# MINIRACER-SD-USB.net
KiCad netlist of a schematic drawn in Altium Designer
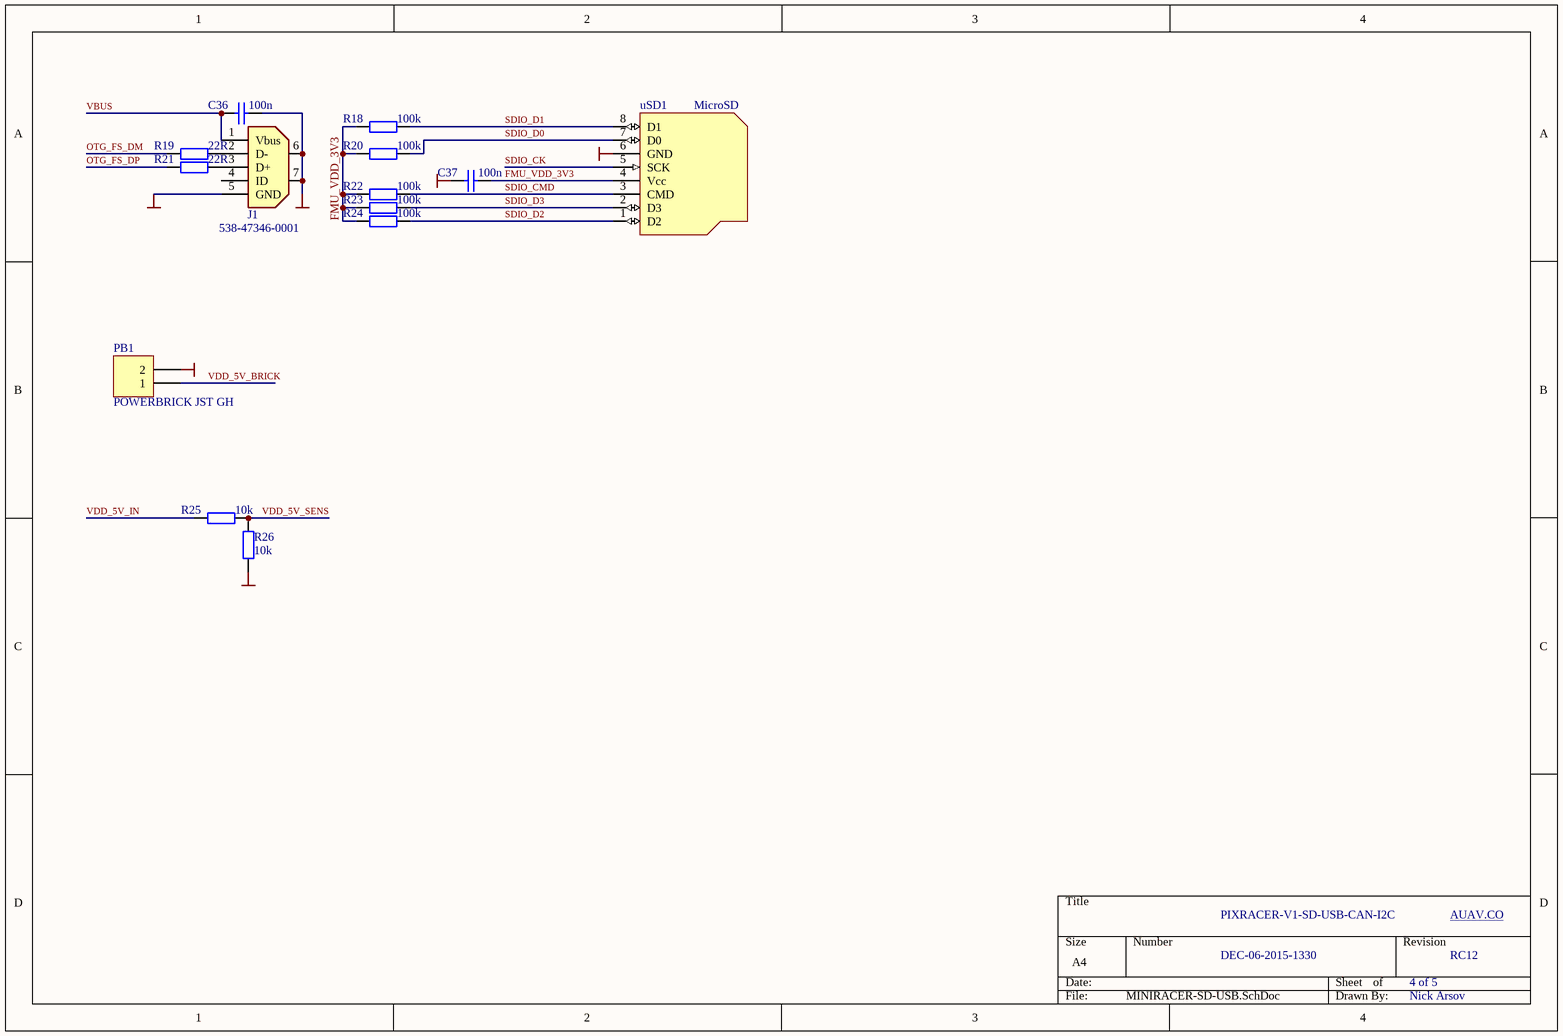
[diagram p0: MINIRACER-SD-USB.SchDoc]

(export (version "E")
  (design (tool "Eeschema 10.0.6"))
  (components
    (comp (ref "C36")
      (value "100n")
      (footprint "0402A")
      (description "Capacitor")
      (fields (field (name "PUBLISHER") "Altium Limited"))
      (libsource (lib "Miscellaneous Devices") (part "Cap"))
    )
    (comp (ref "C37")
      (value "100n")
      (footprint "0402A")
      (description "Capacitor")
      (fields (field (name "PUBLISHER") "Altium Limited"))
      (libsource (lib "Miscellaneous Devices") (part "Cap"))
    )
    (comp (ref "J1")
      (value "miniUSB")
      (footprint "USBmicro_B")
      (fields (field (name "MOUSER PART NUMBER") "538-47346-0001"))
      (libsource (lib "My_Altium") (part "MicroUSB"))
    )
    (comp (ref "PB1")
      (value "POWERBRICK JST GH")
      (footprint "HDR1X2")
      (description "Header, 2-Pin")
      (fields (field (name "PUBLISHER") "Altium Limited"))
      (libsource (lib "Miscellaneous Connectors") (part "Header 2"))
    )
    (comp (ref "R18")
      (value "100k")
      (footprint "0402A")
      (description "Resistor")
      (fields (field (name "PUBLISHER") "Altium Limited"))
      (libsource (lib "Miscellaneous Devices") (part "Res2"))
    )
    (comp (ref "R19")
      (value "22R")
      (footprint "0402A")
      (description "Resistor")
      (fields (field (name "PUBLISHER") "Altium Limited"))
      (libsource (lib "Miscellaneous Devices") (part "Res2"))
    )
    (comp (ref "R20")
      (value "100k")
      (footprint "0402A")
      (description "Resistor")
      (fields (field (name "PUBLISHER") "Altium Limited"))
      (libsource (lib "Miscellaneous Devices") (part "Res2"))
    )
    (comp (ref "R21")
      (value "22R")
      (footprint "0402A")
      (description "Resistor")
      (fields (field (name "PUBLISHER") "Altium Limited"))
      (libsource (lib "Miscellaneous Devices") (part "Res2"))
    )
    (comp (ref "R22")
      (value "100k")
      (footprint "0402A")
      (description "Resistor")
      (fields (field (name "PUBLISHER") "Altium Limited"))
      (libsource (lib "Miscellaneous Devices") (part "Res2"))
    )
    (comp (ref "R23")
      (value "100k")
      (footprint "0402A")
      (description "Resistor")
      (fields (field (name "PUBLISHER") "Altium Limited"))
      (libsource (lib "Miscellaneous Devices") (part "Res2"))
    )
    (comp (ref "R24")
      (value "100k")
      (footprint "0402A")
      (description "Resistor")
      (fields (field (name "PUBLISHER") "Altium Limited"))
      (libsource (lib "Miscellaneous Devices") (part "Res2"))
    )
    (comp (ref "R25")
      (value "10k")
      (footprint "0402A")
      (description "Resistor")
      (fields (field (name "PUBLISHER") "Altium Limited"))
      (libsource (lib "Miscellaneous Devices") (part "Res2"))
    )
    (comp (ref "R26")
      (value "10k")
      (footprint "0402A")
      (description "Resistor")
      (fields (field (name "PUBLISHER") "Altium Limited"))
      (libsource (lib "") (part "Res2_1"))
    )
    (comp (ref "uSD1")
      (value "MicroSD")
      (footprint "MicroSD_China_01")
      (libsource (lib "My_Altium") (part "MicroSD"))
    )
  )
  (nets
    (net (code "1") (name "/FMU_VDD_3V3") (class "Default")
      (node (ref "C37") (pin "1") (pinfunction "1_1") (pintype "passive"))
      (node (ref "R18") (pin "2") (pinfunction "2_2") (pintype "passive"))
      (node (ref "R20") (pin "2") (pinfunction "2_2") (pintype "passive"))
      (node (ref "R22") (pin "2") (pinfunction "2_2") (pintype "passive"))
      (node (ref "R23") (pin "2") (pinfunction "2_2") (pintype "passive"))
      (node (ref "R24") (pin "2") (pinfunction "2_2") (pintype "passive"))
      (node (ref "uSD1") (pin "4") (pinfunction "Vcc_4") (pintype "power_in"))
    )
    (net (code "2") (name "/OTG_FS_DM") (class "Default")
      (node (ref "R19") (pin "2") (pinfunction "2_2") (pintype "passive"))
    )
    (net (code "3") (name "/OTG_FS_DP") (class "Default")
      (node (ref "R21") (pin "2") (pinfunction "2_2") (pintype "passive"))
    )
    (net (code "4") (name "/SDIO_CK") (class "Default")
      (node (ref "uSD1") (pin "5") (pinfunction "SCK_5") (pintype "input"))
    )
    (net (code "5") (name "/SDIO_CMD") (class "Default")
      (node (ref "R22") (pin "1") (pinfunction "1_1") (pintype "passive"))
      (node (ref "uSD1") (pin "3") (pinfunction "CMD_3") (pintype "passive"))
    )
    (net (code "6") (name "/SDIO_D0") (class "Default")
      (node (ref "R20") (pin "1") (pinfunction "1_1") (pintype "passive"))
      (node (ref "uSD1") (pin "7") (pinfunction "D0_7") (pintype "bidirectional"))
    )
    (net (code "7") (name "/SDIO_D1") (class "Default")
      (node (ref "R18") (pin "1") (pinfunction "1_1") (pintype "passive"))
      (node (ref "uSD1") (pin "8") (pinfunction "D1_8") (pintype "bidirectional"))
    )
    (net (code "8") (name "/SDIO_D2") (class "Default")
      (node (ref "R24") (pin "1") (pinfunction "1_1") (pintype "passive"))
      (node (ref "uSD1") (pin "1") (pinfunction "D2_1") (pintype "bidirectional"))
    )
    (net (code "9") (name "/SDIO_D3") (class "Default")
      (node (ref "R23") (pin "1") (pinfunction "1_1") (pintype "passive"))
      (node (ref "uSD1") (pin "2") (pinfunction "D3_2") (pintype "bidirectional"))
    )
    (net (code "10") (name "/VBUS") (class "Default")
      (node (ref "C36") (pin "2") (pinfunction "2_2") (pintype "passive"))
      (node (ref "J1") (pin "1") (pinfunction "Vbus_1") (pintype "power_in"))
    )
    (net (code "11") (name "/VDD_5V_BRICK") (class "Default")
      (node (ref "PB1") (pin "1") (pinfunction "1_1") (pintype "passive"))
    )
    (net (code "12") (name "/VDD_5V_IN") (class "Default")
      (node (ref "R25") (pin "2") (pinfunction "2_2") (pintype "passive"))
    )
    (net (code "13") (name "/VDD_5V_SENS") (class "Default")
      (node (ref "R25") (pin "1") (pinfunction "1_1") (pintype "passive"))
      (node (ref "R26") (pin "1") (pinfunction "1_1") (pintype "passive"))
    )
    (net (code "14") (name "GND") (class "Default")
      (node (ref "C36") (pin "1") (pinfunction "1_1") (pintype "passive"))
      (node (ref "C37") (pin "2") (pinfunction "2_2") (pintype "passive"))
      (node (ref "J1") (pin "5") (pinfunction "GND_5") (pintype "power_in"))
      (node (ref "J1") (pin "6") (pinfunction "GND_6") (pintype "passive"))
      (node (ref "J1") (pin "7") (pinfunction "GND_7") (pintype "passive"))
      (node (ref "PB1") (pin "2") (pinfunction "2_2") (pintype "passive"))
      (node (ref "R26") (pin "2") (pinfunction "2_2") (pintype "passive"))
      (node (ref "uSD1") (pin "6") (pinfunction "GND_6") (pintype "power_in"))
    )
    (net (code "15") (name "Net-(J1-D+)") (class "Default")
      (node (ref "J1") (pin "3") (pinfunction "D+_3") (pintype "passive"))
      (node (ref "R21") (pin "1") (pinfunction "1_1") (pintype "passive"))
    )
    (net (code "16") (name "Net-(J1-D-)") (class "Default")
      (node (ref "J1") (pin "2") (pinfunction "D-_2") (pintype "passive"))
      (node (ref "R19") (pin "1") (pinfunction "1_1") (pintype "passive"))
    )
    (net (code "17") (name "unconnected-(J1-ID-Pad4)") (class "Default")
      (node (ref "J1") (pin "4") (pinfunction "ID_4") (pintype "passive"))
    )
  )
)
